# pc-link.net
KiCad netlist of a schematic drawn in EAGLE
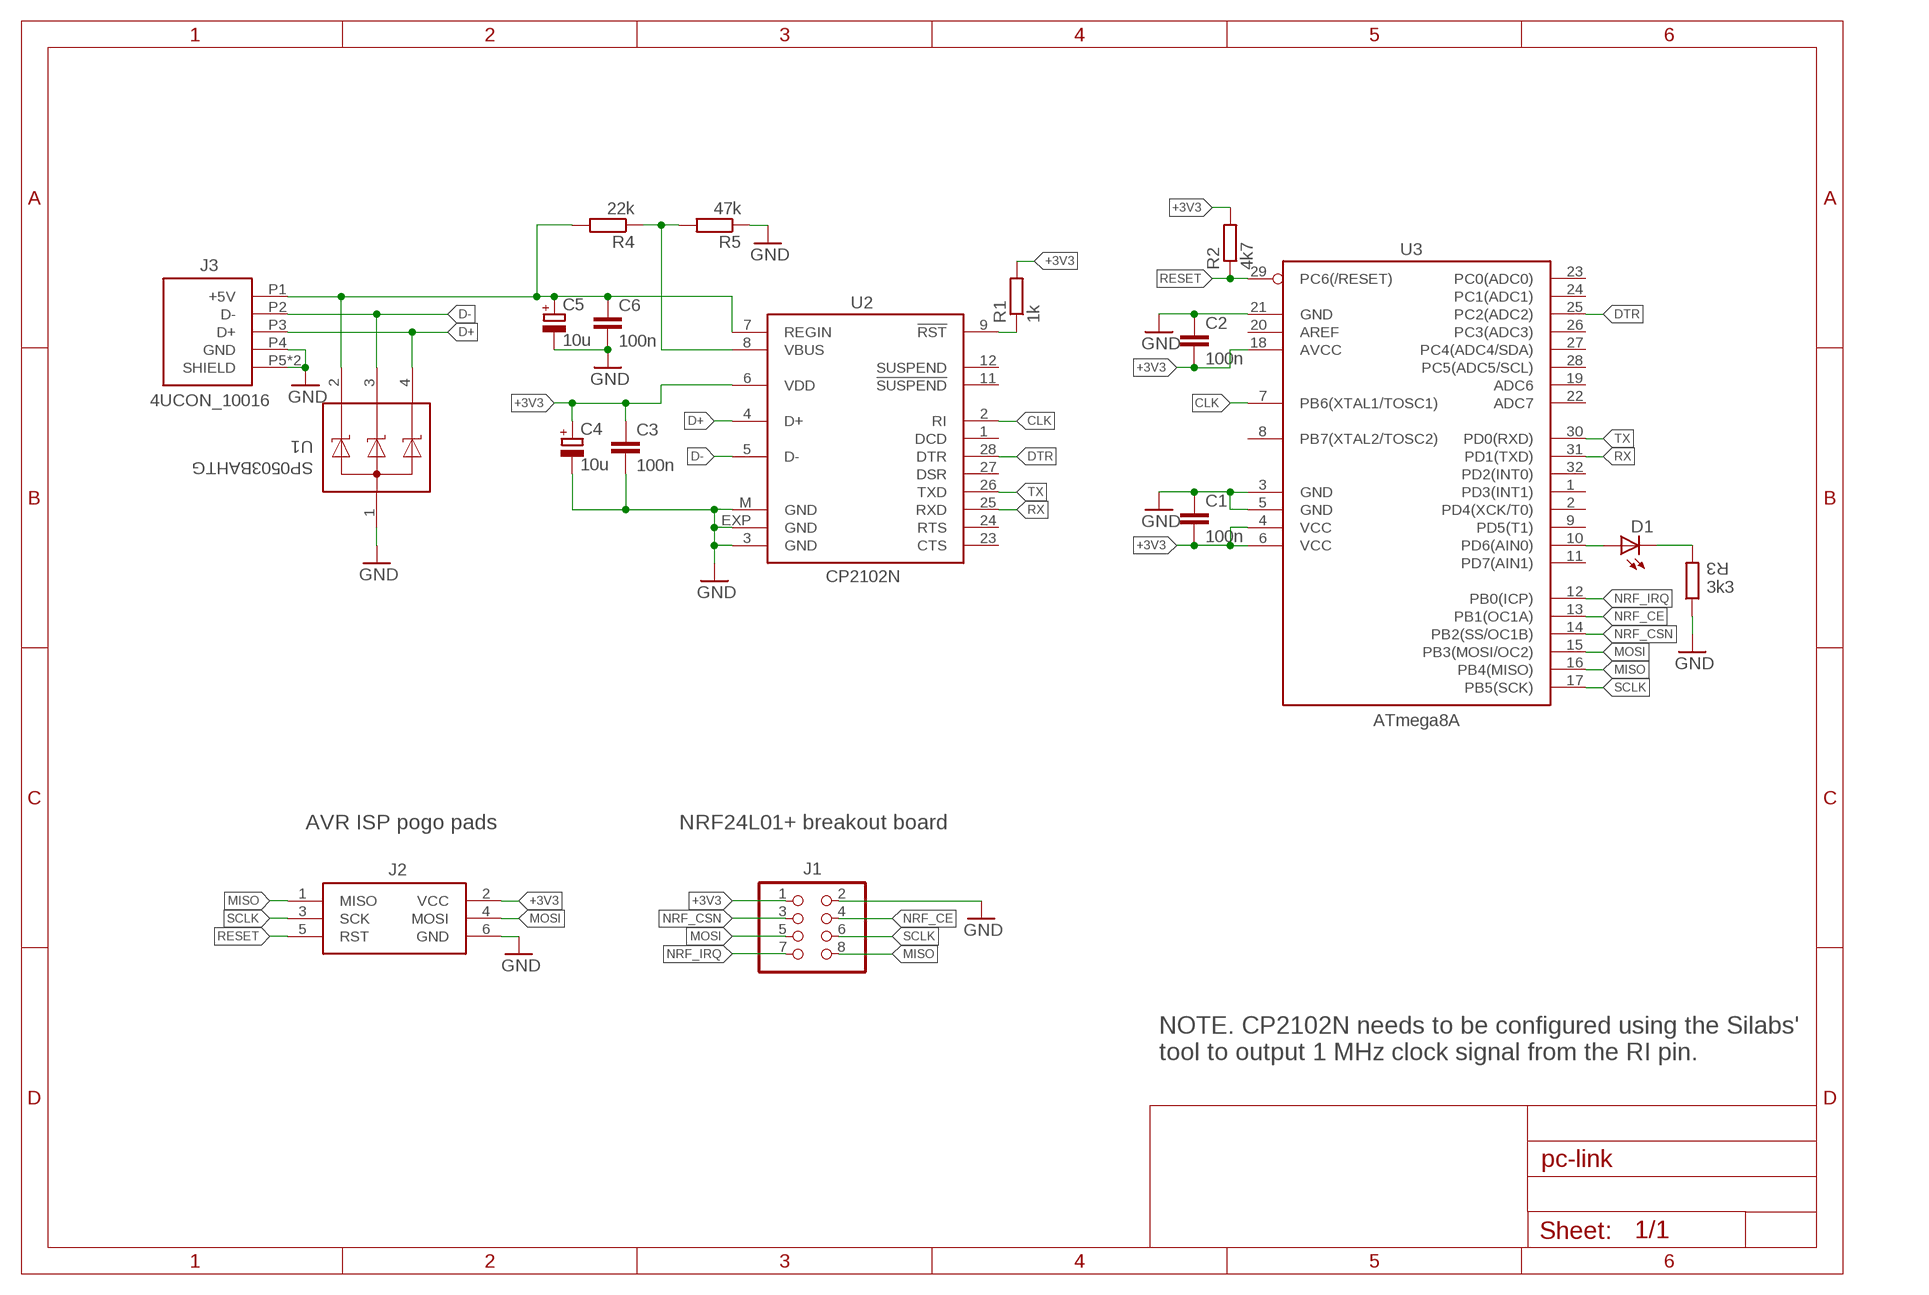
[diagram p0: schematic, sheet 1]

(export (version "E")
  (design (tool "Eeschema 10.0.6"))
  (components
    (comp (ref "C1")
      (value "100n")
      (footprint "eagle-import:C0805")
      (libsource (lib "eagle-import") (part "C-EUC0805"))
    )
    (comp (ref "C2")
      (value "100n")
      (footprint "eagle-import:C0805")
      (libsource (lib "eagle-import") (part "C-EUC0805"))
    )
    (comp (ref "C3")
      (value "100n")
      (footprint "eagle-import:C0805")
      (libsource (lib "eagle-import") (part "C-EUC0805"))
    )
    (comp (ref "C4")
      (value "10u")
      (footprint "eagle-import:CT3216")
      (libsource (lib "eagle-import") (part "CPOL-EUCT3216"))
    )
    (comp (ref "C5")
      (value "10u")
      (footprint "eagle-import:CT3216")
      (libsource (lib "eagle-import") (part "CPOL-EUCT3216"))
    )
    (comp (ref "C6")
      (value "100n")
      (footprint "eagle-import:C0805")
      (libsource (lib "eagle-import") (part "C-EUC0805"))
    )
    (comp (ref "D1")
      (value "LEDSMT1206")
      (footprint "eagle-import:1206")
      (libsource (lib "eagle-import") (part "LEDSMT1206"))
    )
    (comp (ref "J1")
      (value "PINHD-2X4")
      (footprint "eagle-import:2X04")
      (libsource (lib "eagle-import") (part "PINHD-2X4"))
    )
    (comp (ref "J2")
      (value "POGO_AVR_ISP6")
      (footprint "eagle-import:POGO_AVR_ISP6")
      (libsource (lib "eagle-import") (part "POGO_AVR_ISP6"))
    )
    (comp (ref "J3")
      (value "4UCON_10016")
      (footprint "eagle-import:USB_A_4UCON_10016")
      (libsource (lib "eagle-import") (part "USB_A_4UCON_10016"))
    )
    (comp (ref "R1")
      (value "1k")
      (footprint "eagle-import:R0805")
      (libsource (lib "eagle-import") (part "R-EU_R0805"))
    )
    (comp (ref "R2")
      (value "4k7")
      (footprint "eagle-import:R0805")
      (libsource (lib "eagle-import") (part "R-EU_R0805"))
    )
    (comp (ref "R3")
      (value "3k3")
      (footprint "eagle-import:R0805")
      (libsource (lib "eagle-import") (part "R-EU_R0805"))
    )
    (comp (ref "R4")
      (value "22k")
      (footprint "eagle-import:R0805")
      (libsource (lib "eagle-import") (part "R-EU_R0805"))
    )
    (comp (ref "R5")
      (value "47k")
      (footprint "eagle-import:R0805")
      (libsource (lib "eagle-import") (part "R-EU_R0805"))
    )
    (comp (ref "U1")
      (value "SP0503BAHTG")
      (footprint "eagle-import:SOT143")
      (libsource (lib "eagle-import") (part "SP0503BAHTG"))
    )
    (comp (ref "U2")
      (value "CP2102N")
      (footprint "eagle-import:MLP28")
      (fields (field (name "MF") "FARNELL") (field (name "MPN") "CP2102-GM"))
      (libsource (lib "eagle-import") (part "CP2102"))
    )
    (comp (ref "U3")
      (value "ATmega8A")
      (footprint "eagle-import:TQFP32-08")
      (fields (field (name "MPN") "ATMEGA8-16AU"))
      (libsource (lib "eagle-import") (part "MEGA8-AI"))
    )
  )
  (nets
    (net (code "1") (name "+3V3") (class "Default")
      (node (ref "C1") (pin "2") (pinfunction "2_2") (pintype "passive"))
      (node (ref "C2") (pin "2") (pinfunction "2_2") (pintype "passive"))
      (node (ref "C3") (pin "1") (pinfunction "1_1") (pintype "passive"))
      (node (ref "C4") (pin "+") (pinfunction "+_+") (pintype "passive"))
      (node (ref "J1") (pin "1") (pinfunction "1_1") (pintype "passive"))
      (node (ref "J2") (pin "2") (pinfunction "VCC_2") (pintype "bidirectional"))
      (node (ref "R1") (pin "2") (pinfunction "2_2") (pintype "passive"))
      (node (ref "R2") (pin "2") (pinfunction "2_2") (pintype "passive"))
      (node (ref "U2") (pin "6") (pinfunction "VDD_6") (pintype "power_in"))
      (node (ref "U3") (pin "18") (pinfunction "AVCC_18") (pintype "power_in"))
      (node (ref "U3") (pin "4") (pinfunction "VCC_4") (pintype "power_in"))
      (node (ref "U3") (pin "6") (pinfunction "VCC_6") (pintype "power_in"))
    )
    (net (code "2") (name "CLK") (class "Default")
      (node (ref "U2") (pin "2") (pinfunction "RI_2") (pintype "input"))
      (node (ref "U3") (pin "7") (pinfunction "PB6(XTAL1/TOSC1)_7") (pintype "bidirectional"))
    )
    (net (code "3") (name "D+") (class "Default")
      (node (ref "J3") (pin "P3") (pinfunction "D+_P3") (pintype "bidirectional"))
      (node (ref "U1") (pin "4") (pinfunction "P4_4") (pintype "bidirectional"))
      (node (ref "U2") (pin "4") (pinfunction "D+_4") (pintype "bidirectional"))
    )
    (net (code "4") (name "D-") (class "Default")
      (node (ref "J3") (pin "P2") (pinfunction "D-_P2") (pintype "bidirectional"))
      (node (ref "U1") (pin "3") (pinfunction "P3_3") (pintype "bidirectional"))
      (node (ref "U2") (pin "5") (pinfunction "D-_5") (pintype "bidirectional"))
    )
    (net (code "5") (name "DTR") (class "Default")
      (node (ref "U2") (pin "28") (pinfunction "DTR_28") (pintype "output"))
      (node (ref "U3") (pin "25") (pinfunction "PC2(ADC2)_25") (pintype "bidirectional"))
    )
    (net (code "6") (name "GND") (class "Default")
      (node (ref "C1") (pin "1") (pinfunction "1_1") (pintype "passive"))
      (node (ref "C2") (pin "1") (pinfunction "1_1") (pintype "passive"))
      (node (ref "C3") (pin "2") (pinfunction "2_2") (pintype "passive"))
      (node (ref "C4") (pin "-") (pinfunction "-_-") (pintype "passive"))
      (node (ref "C5") (pin "-") (pinfunction "-_-") (pintype "passive"))
      (node (ref "C6") (pin "2") (pinfunction "2_2") (pintype "passive"))
      (node (ref "J1") (pin "2") (pinfunction "2_2") (pintype "passive"))
      (node (ref "J2") (pin "6") (pinfunction "GND_6") (pintype "bidirectional"))
      (node (ref "J3") (pin "P4") (pinfunction "GND_P4") (pintype "bidirectional"))
      (node (ref "J3") (pin "P5") (pinfunction "SHIELD_P5") (pintype "bidirectional"))
      (node (ref "J3") (pin "P6") (pinfunction "SHIELD_P6") (pintype "bidirectional"))
      (node (ref "R3") (pin "1") (pinfunction "1_1") (pintype "passive"))
      (node (ref "R5") (pin "1") (pinfunction "1_1") (pintype "passive"))
      (node (ref "U1") (pin "1") (pinfunction "P1_1") (pintype "bidirectional"))
      (node (ref "U2") (pin "3") (pinfunction "GND_3") (pintype "power_in"))
      (node (ref "U2") (pin "EXP") (pinfunction "GND_EXP") (pintype "power_in"))
      (node (ref "U2") (pin "M") (pinfunction "GND_M") (pintype "power_in"))
      (node (ref "U3") (pin "21") (pinfunction "GND_21") (pintype "power_in"))
      (node (ref "U3") (pin "3") (pinfunction "GND_3") (pintype "power_in"))
      (node (ref "U3") (pin "5") (pinfunction "GND_5") (pintype "power_in"))
    )
    (net (code "7") (name "MISO") (class "Default")
      (node (ref "J1") (pin "8") (pinfunction "8_8") (pintype "passive"))
      (node (ref "J2") (pin "1") (pinfunction "MISO_1") (pintype "bidirectional"))
      (node (ref "U3") (pin "16") (pinfunction "PB4(MISO)_16") (pintype "bidirectional"))
    )
    (net (code "8") (name "MOSI") (class "Default")
      (node (ref "J1") (pin "5") (pinfunction "5_5") (pintype "passive"))
      (node (ref "J2") (pin "4") (pinfunction "MOSI_4") (pintype "bidirectional"))
      (node (ref "U3") (pin "15") (pinfunction "PB3(MOSI/OC2)_15") (pintype "bidirectional"))
    )
    (net (code "9") (name "NRF_CE") (class "Default")
      (node (ref "J1") (pin "4") (pinfunction "4_4") (pintype "passive"))
      (node (ref "U3") (pin "13") (pinfunction "PB1(OC1A)_13") (pintype "bidirectional"))
    )
    (net (code "10") (name "NRF_CSN") (class "Default")
      (node (ref "J1") (pin "3") (pinfunction "3_3") (pintype "passive"))
      (node (ref "U3") (pin "14") (pinfunction "PB2(SS/OC1B)_14") (pintype "bidirectional"))
    )
    (net (code "11") (name "NRF_IRQ") (class "Default")
      (node (ref "J1") (pin "7") (pinfunction "7_7") (pintype "passive"))
      (node (ref "U3") (pin "12") (pinfunction "PB0(ICP)_12") (pintype "bidirectional"))
    )
    (net (code "12") (name "Net-(D1-PadC)") (class "Default")
      (node (ref "D1") (pin "C") (pinfunction "C_C") (pintype "passive"))
      (node (ref "R3") (pin "2") (pinfunction "2_2") (pintype "passive"))
    )
    (net (code "13") (name "Net-(J3-+5V)") (class "Default")
      (node (ref "C5") (pin "+") (pinfunction "+_+") (pintype "passive"))
      (node (ref "C6") (pin "1") (pinfunction "1_1") (pintype "passive"))
      (node (ref "J3") (pin "P1") (pinfunction "+5V_P1") (pintype "bidirectional"))
      (node (ref "R4") (pin "2") (pinfunction "2_2") (pintype "passive"))
      (node (ref "U1") (pin "2") (pinfunction "P2_2") (pintype "bidirectional"))
      (node (ref "U2") (pin "7") (pinfunction "REGIN_7") (pintype "passive"))
    )
    (net (code "14") (name "Net-(U2-VBUS)") (class "Default")
      (node (ref "R4") (pin "1") (pinfunction "1_1") (pintype "passive"))
      (node (ref "R5") (pin "2") (pinfunction "2_2") (pintype "passive"))
      (node (ref "U2") (pin "8") (pinfunction "VBUS_8") (pintype "input"))
    )
    (net (code "15") (name "Net-(U2-~{RST})") (class "Default")
      (node (ref "R1") (pin "1") (pinfunction "1_1") (pintype "passive"))
      (node (ref "U2") (pin "9") (pinfunction "~{RST}_9") (pintype "bidirectional"))
    )
    (net (code "16") (name "Net-(U3-PD6(AIN0))") (class "Default")
      (node (ref "D1") (pin "A") (pinfunction "A_A") (pintype "passive"))
      (node (ref "U3") (pin "10") (pinfunction "PD6(AIN0)_10") (pintype "bidirectional"))
    )
    (net (code "17") (name "RESET") (class "Default")
      (node (ref "J2") (pin "5") (pinfunction "RST_5") (pintype "bidirectional"))
      (node (ref "R2") (pin "1") (pinfunction "1_1") (pintype "passive"))
      (node (ref "U3") (pin "29") (pinfunction "PC6(/RESET)_29") (pintype "bidirectional"))
    )
    (net (code "18") (name "RX") (class "Default")
      (node (ref "U2") (pin "25") (pinfunction "RXD_25") (pintype "input"))
      (node (ref "U3") (pin "31") (pinfunction "PD1(TXD)_31") (pintype "bidirectional"))
    )
    (net (code "19") (name "SCLK") (class "Default")
      (node (ref "J1") (pin "6") (pinfunction "6_6") (pintype "passive"))
      (node (ref "J2") (pin "3") (pinfunction "SCK_3") (pintype "bidirectional"))
      (node (ref "U3") (pin "17") (pinfunction "PB5(SCK)_17") (pintype "bidirectional"))
    )
    (net (code "20") (name "TX") (class "Default")
      (node (ref "U2") (pin "26") (pinfunction "TXD_26") (pintype "output"))
      (node (ref "U3") (pin "30") (pinfunction "PD0(RXD)_30") (pintype "bidirectional"))
    )
    (net (code "21") (name "unconnected-(U2-CTS-Pad23)") (class "Default")
      (node (ref "U2") (pin "23") (pinfunction "CTS_23") (pintype "input"))
    )
    (net (code "22") (name "unconnected-(U2-DCD-Pad1)") (class "Default")
      (node (ref "U2") (pin "1") (pinfunction "DCD_1") (pintype "input"))
    )
    (net (code "23") (name "unconnected-(U2-DSR-Pad27)") (class "Default")
      (node (ref "U2") (pin "27") (pinfunction "DSR_27") (pintype "input"))
    )
    (net (code "24") (name "unconnected-(U2-RTS-Pad24)") (class "Default")
      (node (ref "U2") (pin "24") (pinfunction "RTS_24") (pintype "output"))
    )
    (net (code "25") (name "unconnected-(U2-SUSPEND-Pad12)") (class "Default")
      (node (ref "U2") (pin "12") (pinfunction "SUSPEND_12") (pintype "output"))
    )
    (net (code "26") (name "unconnected-(U2-~{SUSPEND}-Pad11)") (class "Default")
      (node (ref "U2") (pin "11") (pinfunction "~{SUSPEND}_11") (pintype "output"))
    )
    (net (code "27") (name "unconnected-(U3-ADC6-Pad19)") (class "Default")
      (node (ref "U3") (pin "19") (pinfunction "ADC6_19") (pintype "bidirectional"))
    )
    (net (code "28") (name "unconnected-(U3-ADC7-Pad22)") (class "Default")
      (node (ref "U3") (pin "22") (pinfunction "ADC7_22") (pintype "bidirectional"))
    )
    (net (code "29") (name "unconnected-(U3-AREF-Pad20)") (class "Default")
      (node (ref "U3") (pin "20") (pinfunction "AREF_20") (pintype "passive"))
    )
    (net (code "30") (name "unconnected-(U3-PB7(XTAL2{slash}TOSC2)-Pad8)") (class "Default")
      (node (ref "U3") (pin "8") (pinfunction "PB7(XTAL2/TOSC2)_8") (pintype "bidirectional"))
    )
    (net (code "31") (name "unconnected-(U3-PC0(ADC0)-Pad23)") (class "Default")
      (node (ref "U3") (pin "23") (pinfunction "PC0(ADC0)_23") (pintype "bidirectional"))
    )
    (net (code "32") (name "unconnected-(U3-PC1(ADC1)-Pad24)") (class "Default")
      (node (ref "U3") (pin "24") (pinfunction "PC1(ADC1)_24") (pintype "bidirectional"))
    )
    (net (code "33") (name "unconnected-(U3-PC3(ADC3)-Pad26)") (class "Default")
      (node (ref "U3") (pin "26") (pinfunction "PC3(ADC3)_26") (pintype "bidirectional"))
    )
    (net (code "34") (name "unconnected-(U3-PC4(ADC4{slash}SDA)-Pad27)") (class "Default")
      (node (ref "U3") (pin "27") (pinfunction "PC4(ADC4/SDA)_27") (pintype "bidirectional"))
    )
    (net (code "35") (name "unconnected-(U3-PC5(ADC5{slash}SCL)-Pad28)") (class "Default")
      (node (ref "U3") (pin "28") (pinfunction "PC5(ADC5/SCL)_28") (pintype "bidirectional"))
    )
    (net (code "36") (name "unconnected-(U3-PD2(INT0)-Pad32)") (class "Default")
      (node (ref "U3") (pin "32") (pinfunction "PD2(INT0)_32") (pintype "bidirectional"))
    )
    (net (code "37") (name "unconnected-(U3-PD3(INT1)-Pad1)") (class "Default")
      (node (ref "U3") (pin "1") (pinfunction "PD3(INT1)_1") (pintype "bidirectional"))
    )
    (net (code "38") (name "unconnected-(U3-PD4(XCK{slash}T0)-Pad2)") (class "Default")
      (node (ref "U3") (pin "2") (pinfunction "PD4(XCK/T0)_2") (pintype "bidirectional"))
    )
    (net (code "39") (name "unconnected-(U3-PD5(T1)-Pad9)") (class "Default")
      (node (ref "U3") (pin "9") (pinfunction "PD5(T1)_9") (pintype "bidirectional"))
    )
    (net (code "40") (name "unconnected-(U3-PD7(AIN1)-Pad11)") (class "Default")
      (node (ref "U3") (pin "11") (pinfunction "PD7(AIN1)_11") (pintype "bidirectional"))
    )
  )
)
